# FAT42.net
KiCad netlist of a schematic drawn in Altium Designer
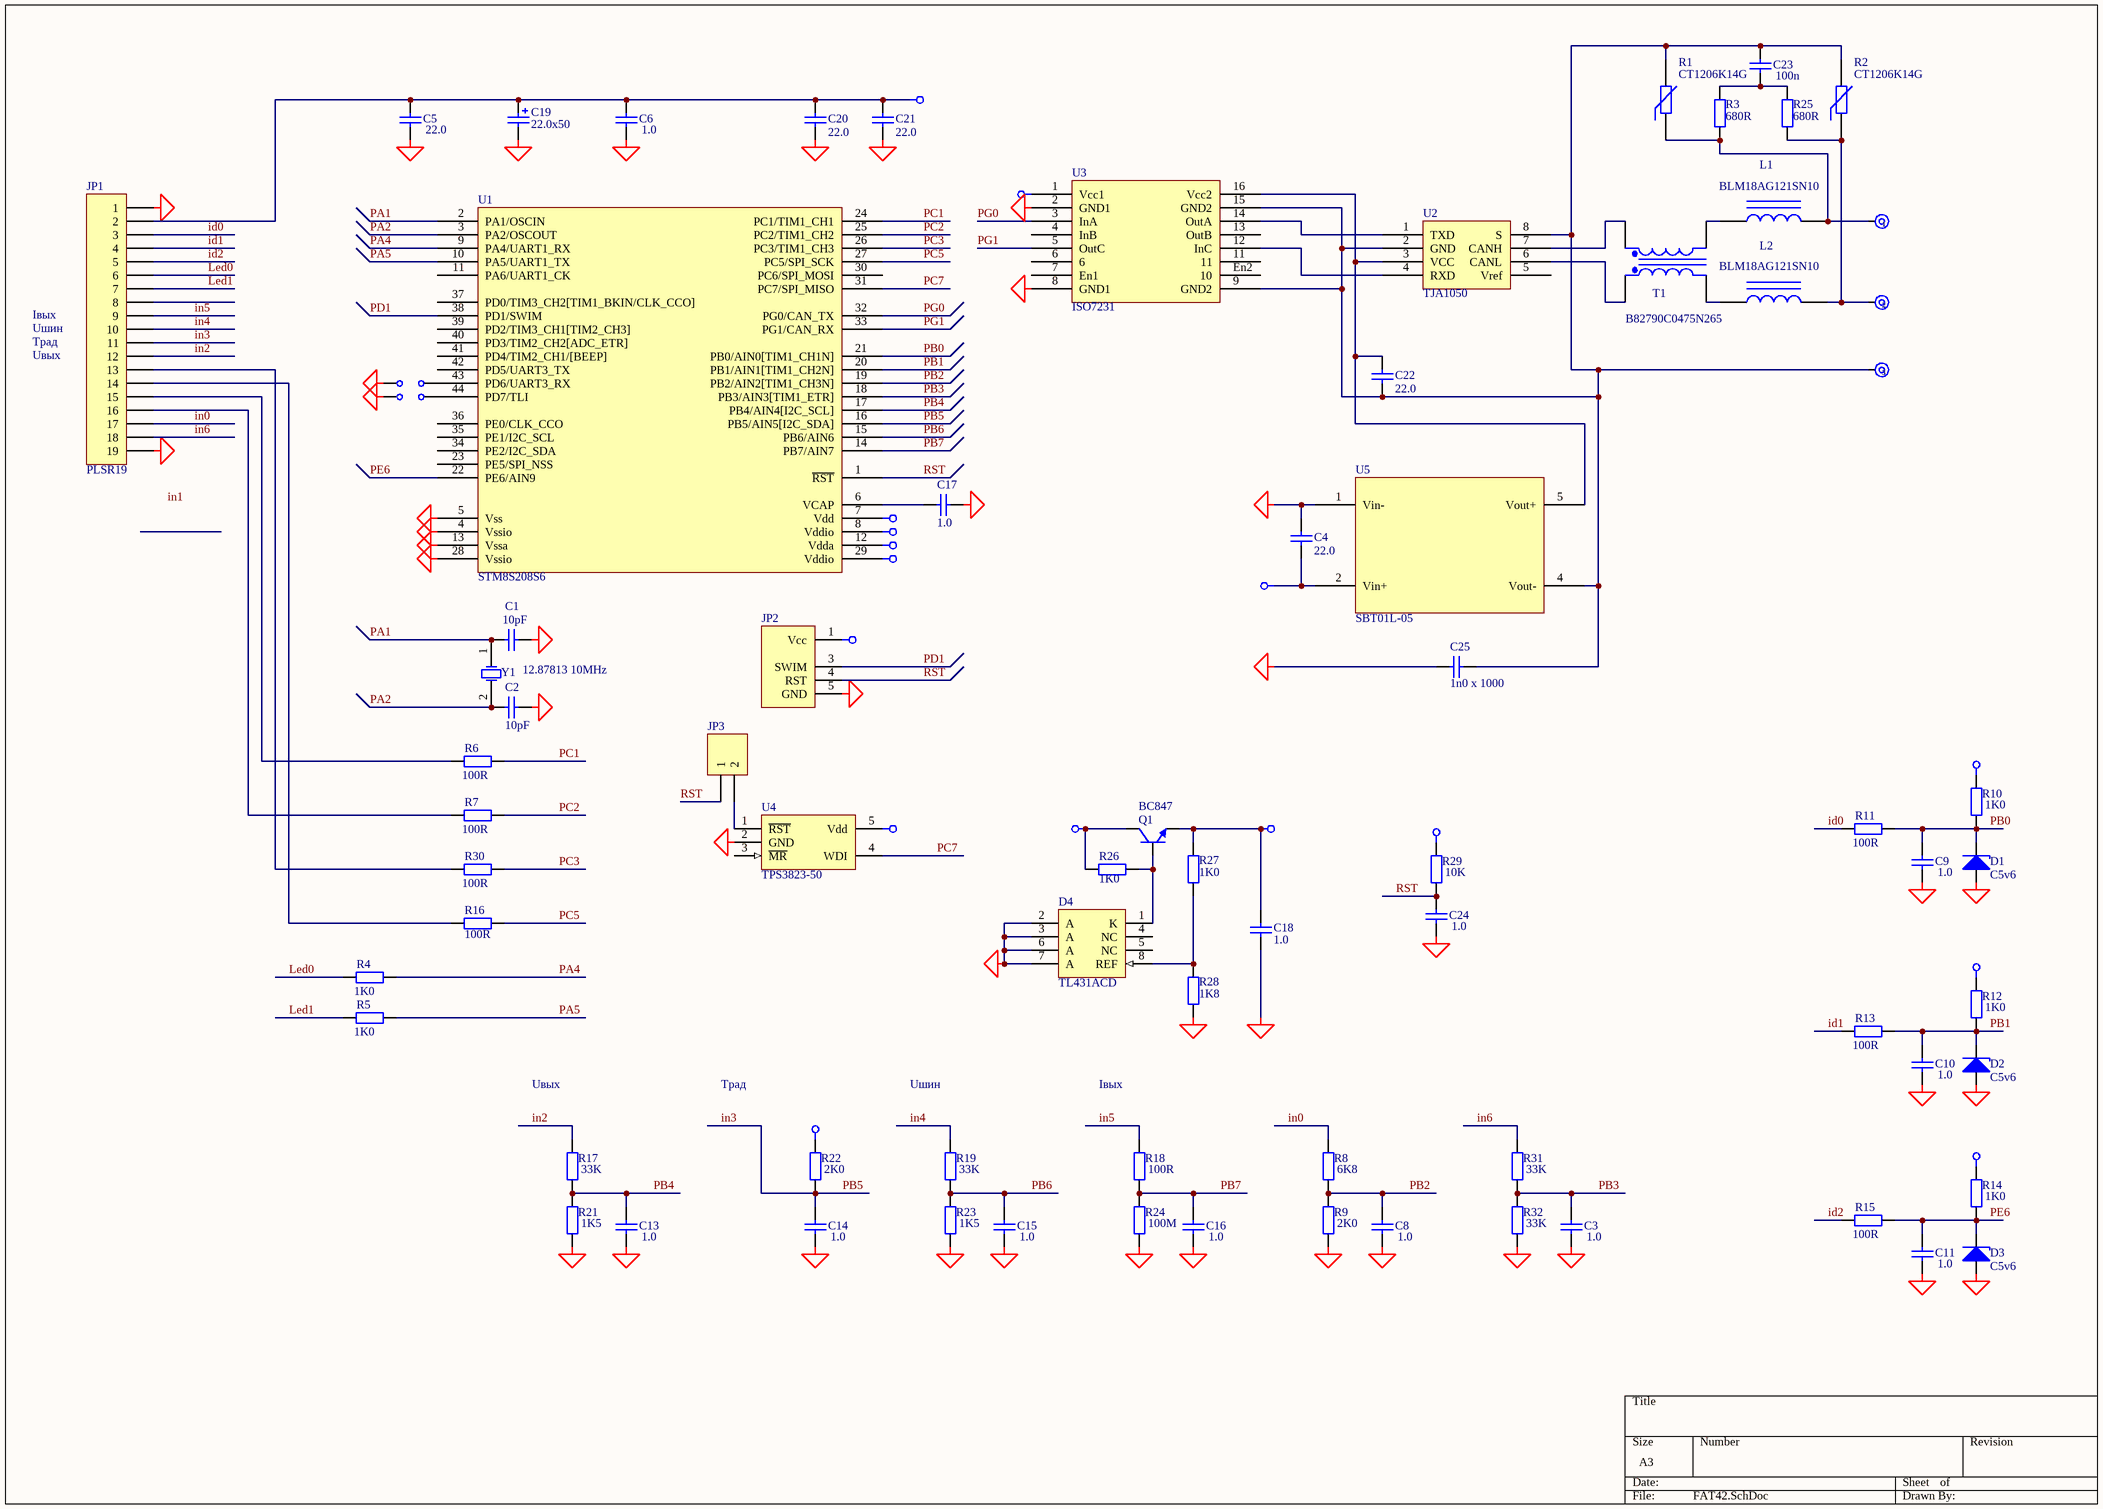
[diagram p0: FAT42.SchDoc]

(export (version "E")
  (design (tool "Eeschema 10.0.6"))
  (components
    (comp (ref "1")
      (value "~")
      (footprint "PIN2R")
      (description "Socket")
      (fields (field (name "MANUFACTURER") "Generic Components") (field (name "PUBLISHER") "Altium Limited"))
      (libsource (lib "PAL") (part "Socket_Ring"))
    )
    (comp (ref "2")
      (value "~")
      (footprint "PIN2R")
      (description "Socket")
      (fields (field (name "MANUFACTURER") "Generic Components") (field (name "PUBLISHER") "Altium Limited"))
      (libsource (lib "PAL") (part "Socket_Ring"))
    )
    (comp (ref "3")
      (value "~")
      (footprint "PIN2R")
      (description "Socket")
      (fields (field (name "MANUFACTURER") "Generic Components") (field (name "PUBLISHER") "Altium Limited"))
      (libsource (lib "PAL") (part "Socket_Ring"))
    )
    (comp (ref "C1")
      (value "10pF")
      (footprint "_0603")
      (description "Capacitor (Semiconductor SIM Model)")
      (fields (field (name "MANUFACTURER") "Generic Components") (field (name "PUBLISHER") "Altium Limited"))
      (libsource (lib "Miscellaneous Devices") (part "Cap Semi"))
    )
    (comp (ref "C2")
      (value "10pF")
      (footprint "_0603")
      (description "Capacitor (Semiconductor SIM Model)")
      (fields (field (name "MANUFACTURER") "Generic Components") (field (name "PUBLISHER") "Altium Limited"))
      (libsource (lib "Miscellaneous Devices") (part "Cap Semi"))
    )
    (comp (ref "C3")
      (value "1.0")
      (footprint "_0603")
      (description "Capacitor (Semiconductor SIM Model)")
      (fields (field (name "MANUFACTURER") "Generic Components") (field (name "PUBLISHER") "Altium Limited"))
      (libsource (lib "Miscellaneous Devices") (part "Cap Semi"))
    )
    (comp (ref "C4")
      (value "22.0")
      (footprint "_1206")
      (description "Capacitor (Semiconductor SIM Model)")
      (fields (field (name "MANUFACTURER") "Generic Components") (field (name "PUBLISHER") "Altium Limited"))
      (libsource (lib "Miscellaneous Devices") (part "Cap Semi"))
    )
    (comp (ref "C5")
      (value "22.0")
      (footprint "_1206")
      (description "Capacitor (Semiconductor SIM Model)")
      (fields (field (name "MANUFACTURER") "Generic Components") (field (name "PUBLISHER") "Altium Limited"))
      (libsource (lib "Miscellaneous Devices") (part "Cap Semi"))
    )
    (comp (ref "C6")
      (value "1.0")
      (footprint "_1206")
      (description "Capacitor (Semiconductor SIM Model)")
      (fields (field (name "MANUFACTURER") "Generic Components") (field (name "PUBLISHER") "Altium Limited"))
      (libsource (lib "Miscellaneous Devices") (part "Cap Semi"))
    )
    (comp (ref "C8")
      (value "1.0")
      (footprint "_0603")
      (description "Capacitor (Semiconductor SIM Model)")
      (fields (field (name "MANUFACTURER") "Generic Components") (field (name "PUBLISHER") "Altium Limited"))
      (libsource (lib "Miscellaneous Devices") (part "Cap Semi"))
    )
    (comp (ref "C9")
      (value "1.0")
      (footprint "_0603")
      (description "Capacitor (Semiconductor SIM Model)")
      (fields (field (name "MANUFACTURER") "Generic Components") (field (name "PUBLISHER") "Altium Limited"))
      (libsource (lib "Miscellaneous Devices") (part "Cap Semi"))
    )
    (comp (ref "C10")
      (value "1.0")
      (footprint "_0603")
      (description "Capacitor (Semiconductor SIM Model)")
      (fields (field (name "MANUFACTURER") "Generic Components") (field (name "PUBLISHER") "Altium Limited"))
      (libsource (lib "Miscellaneous Devices") (part "Cap Semi"))
    )
    (comp (ref "C11")
      (value "1.0")
      (footprint "_0603")
      (description "Capacitor (Semiconductor SIM Model)")
      (fields (field (name "MANUFACTURER") "Generic Components") (field (name "PUBLISHER") "Altium Limited"))
      (libsource (lib "Miscellaneous Devices") (part "Cap Semi"))
    )
    (comp (ref "C13")
      (value "1.0")
      (footprint "_0603")
      (description "Capacitor (Semiconductor SIM Model)")
      (fields (field (name "MANUFACTURER") "Generic Components") (field (name "PUBLISHER") "Altium Limited"))
      (libsource (lib "Miscellaneous Devices") (part "Cap Semi"))
    )
    (comp (ref "C14")
      (value "1.0")
      (footprint "_0603")
      (description "Capacitor (Semiconductor SIM Model)")
      (fields (field (name "MANUFACTURER") "Generic Components") (field (name "PUBLISHER") "Altium Limited"))
      (libsource (lib "Miscellaneous Devices") (part "Cap Semi"))
    )
    (comp (ref "C15")
      (value "1.0")
      (footprint "_0603")
      (description "Capacitor (Semiconductor SIM Model)")
      (fields (field (name "MANUFACTURER") "Generic Components") (field (name "PUBLISHER") "Altium Limited"))
      (libsource (lib "Miscellaneous Devices") (part "Cap Semi"))
    )
    (comp (ref "C16")
      (value "1.0")
      (footprint "_0603")
      (description "Capacitor (Semiconductor SIM Model)")
      (fields (field (name "MANUFACTURER") "Generic Components") (field (name "PUBLISHER") "Altium Limited"))
      (libsource (lib "Miscellaneous Devices") (part "Cap Semi"))
    )
    (comp (ref "C17")
      (value "1.0")
      (footprint "_0603")
      (description "Capacitor (Semiconductor SIM Model)")
      (fields (field (name "MANUFACTURER") "Generic Components") (field (name "PUBLISHER") "Altium Limited"))
      (libsource (lib "Miscellaneous Devices") (part "Cap Semi"))
    )
    (comp (ref "C18")
      (value "1.0")
      (footprint "_0603")
      (description "Capacitor (Semiconductor SIM Model)")
      (fields (field (name "MANUFACTURER") "Generic Components") (field (name "PUBLISHER") "Altium Limited"))
      (libsource (lib "Miscellaneous Devices") (part "Cap Semi"))
    )
    (comp (ref "C19")
      (value "22.0x50")
      (footprint "el3")
      (description "Polarized Capacitor (Radial)")
      (fields (field (name "MANUFACTURER") "Generic Components") (field (name "PUBLISHER") "Altium Limited"))
      (libsource (lib "PAL") (part "Cap Pol1"))
    )
    (comp (ref "C20")
      (value "22.0")
      (footprint "_1206")
      (description "Capacitor (Semiconductor SIM Model)")
      (fields (field (name "MANUFACTURER") "Generic Components") (field (name "PUBLISHER") "Altium Limited"))
      (libsource (lib "Miscellaneous Devices") (part "Cap Semi"))
    )
    (comp (ref "C21")
      (value "22.0")
      (footprint "_1206")
      (description "Capacitor (Semiconductor SIM Model)")
      (fields (field (name "MANUFACTURER") "Generic Components") (field (name "PUBLISHER") "Altium Limited"))
      (libsource (lib "Miscellaneous Devices") (part "Cap Semi"))
    )
    (comp (ref "C22")
      (value "22.0")
      (footprint "_1206")
      (description "Capacitor (Semiconductor SIM Model)")
      (fields (field (name "MANUFACTURER") "Generic Components") (field (name "PUBLISHER") "Altium Limited"))
      (libsource (lib "Miscellaneous Devices") (part "Cap Semi"))
    )
    (comp (ref "C23")
      (value "100n")
      (footprint "_0603")
      (description "Capacitor (Semiconductor SIM Model)")
      (fields (field (name "MANUFACTURER") "Generic Components") (field (name "PUBLISHER") "Altium Limited"))
      (libsource (lib "Miscellaneous Devices") (part "Cap Semi"))
    )
    (comp (ref "C24")
      (value "1.0")
      (footprint "_0603")
      (description "Capacitor (Semiconductor SIM Model)")
      (fields (field (name "MANUFACTURER") "Generic Components") (field (name "PUBLISHER") "Altium Limited"))
      (libsource (lib "Miscellaneous Devices") (part "Cap Semi"))
    )
    (comp (ref "C25")
      (value "1n0 x 1000")
      (footprint "_1206")
      (description "Capacitor (Semiconductor SIM Model)")
      (fields (field (name "MANUFACTURER") "Generic Components") (field (name "PUBLISHER") "Altium Limited"))
      (libsource (lib "Miscellaneous Devices") (part "Cap Semi"))
    )
    (comp (ref "D1")
      (value "C5v6")
      (footprint "_1206d")
      (description "Default Diode")
      (fields (field (name "MANUFACTURER") "Generic Components") (field (name "PUBLISHER") "Altium Limited"))
      (libsource (lib "PAL") (part "Zener"))
    )
    (comp (ref "D2")
      (value "C5v6")
      (footprint "_1206d")
      (description "Default Diode")
      (fields (field (name "MANUFACTURER") "Generic Components") (field (name "PUBLISHER") "Altium Limited"))
      (libsource (lib "PAL") (part "Zener"))
    )
    (comp (ref "D3")
      (value "C5v6")
      (footprint "_1206d")
      (description "Default Diode")
      (fields (field (name "MANUFACTURER") "Generic Components") (field (name "PUBLISHER") "Altium Limited"))
      (libsource (lib "PAL") (part "Zener"))
    )
    (comp (ref "D4")
      (value "TL431ACD")
      (footprint "SO-G8")
      (description "Programmable Precision Reference")
      (fields (field (name "MANUFACTURER") "Motorola") (field (name "PUBLISHER") "Altium Limited"))
      (libsource (lib "Motorola Power Management Voltage Reference") (part "TL431ACD"))
    )
    (comp (ref "J1")
      (value "~")
      (footprint "jmp")
      (description "Switch")
      (fields (field (name "MANUFACTURER") "Generic Components") (field (name "PUBLISHER") "Altium Limited"))
      (libsource (lib "PAL") (part "JMP"))
    )
    (comp (ref "J2")
      (value "~")
      (footprint "jmp")
      (description "Switch")
      (fields (field (name "MANUFACTURER") "Generic Components") (field (name "PUBLISHER") "Altium Limited"))
      (libsource (lib "PAL") (part "JMP"))
    )
    (comp (ref "JP1")
      (value "PLSR19")
      (footprint "HDR1X19")
      (description "Header, 19-Pin")
      (fields (field (name "MANUFACTURER") "Generic Components") (field (name "PUBLISHER") "Altium Limited"))
      (libsource (lib "Miscellaneous Connectors") (part "Header 19"))
    )
    (comp (ref "JP2") (value "~") (footprint "HDR1X5_uart") (libsource (lib "PAL") (part "SWIM_CONN")))
    (comp (ref "JP3")
      (value "PLS2")
      (footprint "HDR1X2")
      (description "Header, 2-Pin")
      (fields (field (name "MANUFACTURER") "Generic Components") (field (name "PUBLISHER") "Altium Limited"))
      (libsource (lib "Miscellaneous Connectors") (part "Header 2"))
    )
    (comp (ref "L1")
      (value "BLM18AG121SN10")
      (footprint "_1206")
      (description "Magnetic-Core Inductor")
      (fields (field (name "MANUFACTURER") "Generic Components") (field (name "PUBLISHER") "Altium Limited"))
      (libsource (lib "Miscellaneous Devices") (part "Inductor Iron"))
    )
    (comp (ref "L2")
      (value "BLM18AG121SN10")
      (footprint "_1206")
      (description "Magnetic-Core Inductor")
      (fields (field (name "MANUFACTURER") "Generic Components") (field (name "PUBLISHER") "Altium Limited"))
      (libsource (lib "Miscellaneous Devices") (part "Inductor Iron"))
    )
    (comp (ref "Q1")
      (value "BC847")
      (footprint "SO-G3")
      (description "General Purpose Transistor NPN Silicon")
      (fields (field (name "MANUFACTURER") "Motorola") (field (name "PUBLISHER") "Altium Limited"))
      (libsource (lib "PAL") (part "BC847ALT1"))
    )
    (comp (ref "R1")
      (value "CT1206K14G")
      (footprint "_1206")
      (description "Varistor (Voltage-Sensitive Resistor)")
      (fields (field (name "MANUFACTURER") "Generic Components") (field (name "PUBLISHER") "Altium Limited"))
      (libsource (lib "Miscellaneous Devices") (part "Res Varistor"))
    )
    (comp (ref "R2")
      (value "CT1206K14G")
      (footprint "_1206")
      (description "Varistor (Voltage-Sensitive Resistor)")
      (fields (field (name "MANUFACTURER") "Generic Components") (field (name "PUBLISHER") "Altium Limited"))
      (libsource (lib "Miscellaneous Devices") (part "Res Varistor"))
    )
    (comp (ref "R3")
      (value "680R")
      (footprint "_0603")
      (description "Resistor")
      (fields (field (name "MANUFACTURER") "Generic Components") (field (name "PUBLISHER") "Altium Limited"))
      (libsource (lib "Miscellaneous Devices") (part "Res2"))
    )
    (comp (ref "R4")
      (value "1K0")
      (footprint "_0603")
      (description "Resistor")
      (fields (field (name "MANUFACTURER") "Generic Components") (field (name "PUBLISHER") "Altium Limited"))
      (libsource (lib "Miscellaneous Devices") (part "Res2"))
    )
    (comp (ref "R5")
      (value "1K0")
      (footprint "_0603")
      (description "Resistor")
      (fields (field (name "MANUFACTURER") "Generic Components") (field (name "PUBLISHER") "Altium Limited"))
      (libsource (lib "Miscellaneous Devices") (part "Res2"))
    )
    (comp (ref "R6")
      (value "100R")
      (footprint "_0603")
      (description "Resistor")
      (fields (field (name "MANUFACTURER") "Generic Components") (field (name "PUBLISHER") "Altium Limited"))
      (libsource (lib "") (part "Res2_2"))
    )
    (comp (ref "R7")
      (value "100R")
      (footprint "_0603")
      (description "Resistor")
      (fields (field (name "MANUFACTURER") "Generic Components") (field (name "PUBLISHER") "Altium Limited"))
      (libsource (lib "") (part "Res2_2"))
    )
    (comp (ref "R8")
      (value "6K8")
      (footprint "_0603")
      (description "Resistor")
      (fields (field (name "MANUFACTURER") "Generic Components") (field (name "PUBLISHER") "Altium Limited"))
      (libsource (lib "") (part "Res2_1"))
    )
    (comp (ref "R9")
      (value "2K0")
      (footprint "_0603")
      (description "Resistor")
      (fields (field (name "MANUFACTURER") "Generic Components") (field (name "PUBLISHER") "Altium Limited"))
      (libsource (lib "") (part "Res2_1"))
    )
    (comp (ref "R10")
      (value "1K0")
      (footprint "_0603")
      (description "Resistor")
      (fields (field (name "MANUFACTURER") "Generic Components") (field (name "PUBLISHER") "Altium Limited"))
      (libsource (lib "") (part "Res2_3"))
    )
    (comp (ref "R11")
      (value "100R")
      (footprint "_0603")
      (description "Resistor")
      (fields (field (name "MANUFACTURER") "Generic Components") (field (name "PUBLISHER") "Altium Limited"))
      (libsource (lib "") (part "Res2_2"))
    )
    (comp (ref "R12")
      (value "1K0")
      (footprint "_0603")
      (description "Resistor")
      (fields (field (name "MANUFACTURER") "Generic Components") (field (name "PUBLISHER") "Altium Limited"))
      (libsource (lib "") (part "Res2_3"))
    )
    (comp (ref "R13")
      (value "100R")
      (footprint "_0603")
      (description "Resistor")
      (fields (field (name "MANUFACTURER") "Generic Components") (field (name "PUBLISHER") "Altium Limited"))
      (libsource (lib "") (part "Res2_2"))
    )
    (comp (ref "R14")
      (value "1K0")
      (footprint "_0603")
      (description "Resistor")
      (fields (field (name "MANUFACTURER") "Generic Components") (field (name "PUBLISHER") "Altium Limited"))
      (libsource (lib "") (part "Res2_3"))
    )
    (comp (ref "R15")
      (value "100R")
      (footprint "_0603")
      (description "Resistor")
      (fields (field (name "MANUFACTURER") "Generic Components") (field (name "PUBLISHER") "Altium Limited"))
      (libsource (lib "") (part "Res2_2"))
    )
    (comp (ref "R16")
      (value "100R")
      (footprint "_0603")
      (description "Resistor")
      (fields (field (name "MANUFACTURER") "Generic Components") (field (name "PUBLISHER") "Altium Limited"))
      (libsource (lib "") (part "Res2_2"))
    )
    (comp (ref "R17")
      (value "33K")
      (footprint "_1206")
      (description "Resistor")
      (fields (field (name "MANUFACTURER") "Generic Components") (field (name "PUBLISHER") "Altium Limited"))
      (libsource (lib "") (part "Res2_1"))
    )
    (comp (ref "R18")
      (value "100R")
      (footprint "_0603")
      (description "Resistor")
      (fields (field (name "MANUFACTURER") "Generic Components") (field (name "PUBLISHER") "Altium Limited"))
      (libsource (lib "") (part "Res2_1"))
    )
    (comp (ref "R19")
      (value "33K")
      (footprint "_1206")
      (description "Resistor")
      (fields (field (name "MANUFACTURER") "Generic Components") (field (name "PUBLISHER") "Altium Limited"))
      (libsource (lib "") (part "Res2_1"))
    )
    (comp (ref "R21")
      (value "1K5")
      (footprint "_0603")
      (description "Resistor")
      (fields (field (name "MANUFACTURER") "Generic Components") (field (name "PUBLISHER") "Altium Limited"))
      (libsource (lib "") (part "Res2_1"))
    )
    (comp (ref "R22")
      (value "2K0")
      (footprint "_0603")
      (description "Resistor")
      (fields (field (name "MANUFACTURER") "Generic Components") (field (name "PUBLISHER") "Altium Limited"))
      (libsource (lib "") (part "Res2_1"))
    )
    (comp (ref "R23")
      (value "1K5")
      (footprint "_0603")
      (description "Resistor")
      (fields (field (name "MANUFACTURER") "Generic Components") (field (name "PUBLISHER") "Altium Limited"))
      (libsource (lib "") (part "Res2_1"))
    )
    (comp (ref "R24")
      (value "100M")
      (footprint "_0603")
      (description "Resistor")
      (fields (field (name "MANUFACTURER") "Generic Components") (field (name "PUBLISHER") "Altium Limited"))
      (libsource (lib "") (part "Res2_1"))
    )
    (comp (ref "R25")
      (value "680R")
      (footprint "_0603")
      (description "Resistor")
      (fields (field (name "MANUFACTURER") "Generic Components") (field (name "PUBLISHER") "Altium Limited"))
      (libsource (lib "Miscellaneous Devices") (part "Res2"))
    )
    (comp (ref "R26")
      (value "1K0")
      (footprint "_0603")
      (description "Resistor")
      (fields (field (name "MANUFACTURER") "Generic Components") (field (name "PUBLISHER") "Altium Limited"))
      (libsource (lib "") (part "Res2_4"))
    )
    (comp (ref "R27")
      (value "1K0")
      (footprint "_0603")
      (description "Resistor")
      (fields (field (name "MANUFACTURER") "Generic Components") (field (name "PUBLISHER") "Altium Limited"))
      (libsource (lib "Miscellaneous Devices") (part "Res2"))
    )
    (comp (ref "R28")
      (value "1K8")
      (footprint "_0603")
      (description "Resistor")
      (fields (field (name "MANUFACTURER") "Generic Components") (field (name "PUBLISHER") "Altium Limited"))
      (libsource (lib "Miscellaneous Devices") (part "Res2"))
    )
    (comp (ref "R29")
      (value "10K")
      (footprint "_0603")
      (description "Resistor")
      (fields (field (name "MANUFACTURER") "Generic Components") (field (name "PUBLISHER") "Altium Limited"))
      (libsource (lib "") (part "Res2_3"))
    )
    (comp (ref "R30")
      (value "100R")
      (footprint "_0603")
      (description "Resistor")
      (fields (field (name "MANUFACTURER") "Generic Components") (field (name "PUBLISHER") "Altium Limited"))
      (libsource (lib "") (part "Res2_2"))
    )
    (comp (ref "R31")
      (value "33K")
      (footprint "_0603")
      (description "Resistor")
      (fields (field (name "MANUFACTURER") "Generic Components") (field (name "PUBLISHER") "Altium Limited"))
      (libsource (lib "") (part "Res2_1"))
    )
    (comp (ref "R32")
      (value "33K")
      (footprint "_0603")
      (description "Resistor")
      (fields (field (name "MANUFACTURER") "Generic Components") (field (name "PUBLISHER") "Altium Limited"))
      (libsource (lib "") (part "Res2_1"))
    )
    (comp (ref "T1")
      (value "B82790C0475N265")
      (footprint "B82790")
      (description "Transformer (Coupled Inductor Model)")
      (fields (field (name "MANUFACTURER") "Generic Components") (field (name "PUBLISHER") "Altium Limited"))
      (libsource (lib "Miscellaneous Devices") (part "Trans Cupl"))
    )
    (comp (ref "U1")
      (value "STM8S208S6")
      (footprint "QFP10X10-G44/G10N")
      (libsource (lib "PAL") (part "STM8S208S6"))
    )
    (comp (ref "U2") (value "TJA1050") (footprint "SO-G8/D5") (libsource (lib "PAL") (part "TJA1050")))
    (comp (ref "U3") (value "ISO7231") (footprint "SO-G16/D10.4") (libsource (lib "PAL") (part "ISO7231")))
    (comp (ref "U4")
      (value "TPS3823-50")
      (footprint "SO-G5/P.95")
      (description "Reset IC")
      (fields
        (field (name "MANUFACTURER") "National Semiconductor")
        (field (name "PUBLISHER") "Altium Limited")
      )
      (libsource (lib "PAL") (part "TPS3823"))
    )
    (comp (ref "U5") (value "SBT01L-05") (footprint "SBT01L") (libsource (lib "PAL") (part "SBT01L")))
    (comp (ref "Y1")
      (value "12.87813 10MHz")
      (footprint "hc49/us")
      (description "Crystal Oscillator")
      (fields (field (name "MANUFACTURER") "Generic Components") (field (name "PUBLISHER") "Altium Limited"))
      (libsource (lib "Miscellaneous Devices") (part "XTAL"))
    )
  )
  (nets
    (net (code "1") (name "+5v") (class "Default")
      (node (ref "C19") (pin "1") (pinfunction "1_1") (pintype "passive"))
      (node (ref "C20") (pin "1") (pinfunction "1_1") (pintype "passive"))
      (node (ref "C21") (pin "1") (pinfunction "1_1") (pintype "passive"))
      (node (ref "C4") (pin "2") (pinfunction "2_2") (pintype "passive"))
      (node (ref "C5") (pin "2") (pinfunction "2_2") (pintype "passive"))
      (node (ref "C6") (pin "2") (pinfunction "2_2") (pintype "passive"))
      (node (ref "JP1") (pin "2") (pinfunction "2_2") (pintype "passive"))
      (node (ref "JP2") (pin "1") (pinfunction "Vcc_1") (pintype "passive"))
      (node (ref "Q1") (pin "3") (pinfunction "C_3") (pintype "passive"))
      (node (ref "R10") (pin "1") (pinfunction "1_1") (pintype "passive"))
      (node (ref "R12") (pin "1") (pinfunction "1_1") (pintype "passive"))
      (node (ref "R14") (pin "1") (pinfunction "1_1") (pintype "passive"))
      (node (ref "R22") (pin "2") (pinfunction "2_2") (pintype "passive"))
      (node (ref "R26") (pin "1") (pinfunction "1_1") (pintype "passive"))
      (node (ref "R29") (pin "1") (pinfunction "1_1") (pintype "passive"))
      (node (ref "U1") (pin "29") (pinfunction "Vddio_29") (pintype "passive"))
      (node (ref "U1") (pin "7") (pinfunction "Vdd_7") (pintype "passive"))
      (node (ref "U1") (pin "8") (pinfunction "Vddio_8") (pintype "passive"))
      (node (ref "U3") (pin "1") (pinfunction "Vcc1_1") (pintype "passive"))
      (node (ref "U4") (pin "5") (pinfunction "Vdd_5") (pintype "power_in"))
      (node (ref "U5") (pin "2") (pinfunction "Vin+_2") (pintype "passive"))
    )
    (net (code "2") (name "/Led0") (class "Default")
      (node (ref "JP1") (pin "6") (pinfunction "6_6") (pintype "passive"))
      (node (ref "R4") (pin "1") (pinfunction "1_1") (pintype "passive"))
    )
    (net (code "3") (name "/Led1") (class "Default")
      (node (ref "JP1") (pin "7") (pinfunction "7_7") (pintype "passive"))
      (node (ref "R5") (pin "1") (pinfunction "1_1") (pintype "passive"))
    )
    (net (code "4") (name "/PA1") (class "Default")
      (node (ref "C1") (pin "2") (pinfunction "2_2") (pintype "passive"))
      (node (ref "U1") (pin "2") (pinfunction "PA1/OSCIN_2") (pintype "passive"))
      (node (ref "Y1") (pin "1") (pinfunction "OSC1_1") (pintype "passive"))
    )
    (net (code "5") (name "/PA2") (class "Default")
      (node (ref "C2") (pin "2") (pinfunction "2_2") (pintype "passive"))
      (node (ref "U1") (pin "3") (pinfunction "PA2/OSCOUT_3") (pintype "passive"))
      (node (ref "Y1") (pin "2") (pinfunction "OSC2_2") (pintype "passive"))
    )
    (net (code "6") (name "/PA4") (class "Default")
      (node (ref "R4") (pin "2") (pinfunction "2_2") (pintype "passive"))
      (node (ref "U1") (pin "9") (pinfunction "PA4/UART1_RX_9") (pintype "passive"))
    )
    (net (code "7") (name "/PA5") (class "Default")
      (node (ref "R5") (pin "2") (pinfunction "2_2") (pintype "passive"))
      (node (ref "U1") (pin "10") (pinfunction "PA5/UART1_TX_10") (pintype "passive"))
    )
    (net (code "8") (name "/PB0") (class "Default")
      (node (ref "C9") (pin "2") (pinfunction "2_2") (pintype "passive"))
      (node (ref "D1") (pin "2") (pinfunction "K_2") (pintype "passive"))
      (node (ref "R10") (pin "2") (pinfunction "2_2") (pintype "passive"))
      (node (ref "R11") (pin "1") (pinfunction "1_1") (pintype "passive"))
      (node (ref "U1") (pin "21") (pinfunction "PB0/AIN0[TIM1_CH1N]_21") (pintype "passive"))
    )
    (net (code "9") (name "/PB1") (class "Default")
      (node (ref "C10") (pin "2") (pinfunction "2_2") (pintype "passive"))
      (node (ref "D2") (pin "2") (pinfunction "K_2") (pintype "passive"))
      (node (ref "R12") (pin "2") (pinfunction "2_2") (pintype "passive"))
      (node (ref "R13") (pin "1") (pinfunction "1_1") (pintype "passive"))
      (node (ref "U1") (pin "20") (pinfunction "PB1/AIN1[TIM1_CH2N]_20") (pintype "passive"))
    )
    (net (code "10") (name "/PB2") (class "Default")
      (node (ref "C8") (pin "2") (pinfunction "2_2") (pintype "passive"))
      (node (ref "R8") (pin "1") (pinfunction "1_1") (pintype "passive"))
      (node (ref "R9") (pin "2") (pinfunction "2_2") (pintype "passive"))
      (node (ref "U1") (pin "19") (pinfunction "PB2/AIN2[TIM1_CH3N]_19") (pintype "passive"))
    )
    (net (code "11") (name "/PB3") (class "Default")
      (node (ref "C3") (pin "2") (pinfunction "2_2") (pintype "passive"))
      (node (ref "R31") (pin "1") (pinfunction "1_1") (pintype "passive"))
      (node (ref "R32") (pin "2") (pinfunction "2_2") (pintype "passive"))
      (node (ref "U1") (pin "18") (pinfunction "PB3/AIN3[TIM1_ETR]_18") (pintype "passive"))
    )
    (net (code "12") (name "/PB4") (class "Default")
      (node (ref "C13") (pin "2") (pinfunction "2_2") (pintype "passive"))
      (node (ref "R17") (pin "1") (pinfunction "1_1") (pintype "passive"))
      (node (ref "R21") (pin "2") (pinfunction "2_2") (pintype "passive"))
      (node (ref "U1") (pin "17") (pinfunction "PB4/AIN4[I2C_SCL]_17") (pintype "passive"))
    )
    (net (code "13") (name "/PB5") (class "Default")
      (node (ref "C14") (pin "2") (pinfunction "2_2") (pintype "passive"))
      (node (ref "JP1") (pin "11") (pinfunction "11_11") (pintype "passive"))
      (node (ref "R22") (pin "1") (pinfunction "1_1") (pintype "passive"))
      (node (ref "U1") (pin "16") (pinfunction "PB5/AIN5[I2C_SDA]_16") (pintype "passive"))
    )
    (net (code "14") (name "/PB6") (class "Default")
      (node (ref "C15") (pin "2") (pinfunction "2_2") (pintype "passive"))
      (node (ref "R19") (pin "1") (pinfunction "1_1") (pintype "passive"))
      (node (ref "R23") (pin "2") (pinfunction "2_2") (pintype "passive"))
      (node (ref "U1") (pin "15") (pinfunction "PB6/AIN6_15") (pintype "passive"))
    )
    (net (code "15") (name "/PB7") (class "Default")
      (node (ref "C16") (pin "2") (pinfunction "2_2") (pintype "passive"))
      (node (ref "R18") (pin "1") (pinfunction "1_1") (pintype "passive"))
      (node (ref "R24") (pin "2") (pinfunction "2_2") (pintype "passive"))
      (node (ref "U1") (pin "14") (pinfunction "PB7/AIN7_14") (pintype "passive"))
    )
    (net (code "16") (name "/PC1") (class "Default")
      (node (ref "R6") (pin "1") (pinfunction "1_1") (pintype "passive"))
      (node (ref "U1") (pin "24") (pinfunction "PC1/TIM1_CH1_24") (pintype "passive"))
    )
    (net (code "17") (name "/PC2") (class "Default")
      (node (ref "R7") (pin "1") (pinfunction "1_1") (pintype "passive"))
      (node (ref "U1") (pin "25") (pinfunction "PC2/TIM1_CH2_25") (pintype "passive"))
    )
    (net (code "18") (name "/PC3") (class "Default")
      (node (ref "R30") (pin "1") (pinfunction "1_1") (pintype "passive"))
      (node (ref "U1") (pin "26") (pinfunction "PC3/TIM1_CH3_26") (pintype "passive"))
    )
    (net (code "19") (name "/PC5") (class "Default")
      (node (ref "R16") (pin "1") (pinfunction "1_1") (pintype "passive"))
      (node (ref "U1") (pin "27") (pinfunction "PC5/SPI_SCK_27") (pintype "passive"))
    )
    (net (code "20") (name "/PC7") (class "Default")
      (node (ref "U1") (pin "31") (pinfunction "PC7/SPI_MISO_31") (pintype "passive"))
      (node (ref "U4") (pin "4") (pinfunction "WDI_4") (pintype "passive"))
    )
    (net (code "21") (name "/PD1") (class "Default")
      (node (ref "JP2") (pin "3") (pinfunction "SWIM_3") (pintype "passive"))
      (node (ref "U1") (pin "38") (pinfunction "PD1/SWIM_38") (pintype "passive"))
    )
    (net (code "22") (name "/PE6") (class "Default")
      (node (ref "C11") (pin "2") (pinfunction "2_2") (pintype "passive"))
      (node (ref "D3") (pin "2") (pinfunction "K_2") (pintype "passive"))
      (node (ref "R14") (pin "2") (pinfunction "2_2") (pintype "passive"))
      (node (ref "R15") (pin "1") (pinfunction "1_1") (pintype "passive"))
      (node (ref "U1") (pin "22") (pinfunction "PE6/AIN9_22") (pintype "passive"))
    )
    (net (code "23") (name "/PG0") (class "Default")
      (node (ref "U1") (pin "32") (pinfunction "PG0/CAN_TX_32") (pintype "passive"))
      (node (ref "U3") (pin "3") (pinfunction "InA_3") (pintype "passive"))
    )
    (net (code "24") (name "/PG1") (class "Default")
      (node (ref "U1") (pin "33") (pinfunction "PG1/CAN_RX_33") (pintype "passive"))
      (node (ref "U3") (pin "5") (pinfunction "OutC_5") (pintype "passive"))
    )
    (net (code "25") (name "/RST") (class "Default")
      (node (ref "C24") (pin "2") (pinfunction "2_2") (pintype "passive"))
      (node (ref "JP2") (pin "4") (pinfunction "RST_4") (pintype "passive"))
      (node (ref "JP3") (pin "1") (pinfunction "1_1") (pintype "passive"))
      (node (ref "R29") (pin "2") (pinfunction "2_2") (pintype "passive"))
      (node (ref "U1") (pin "1") (pinfunction "~{RST}_1") (pintype "passive"))
    )
    (net (code "26") (name "/id0") (class "Default")
      (node (ref "JP1") (pin "3") (pinfunction "3_3") (pintype "passive"))
      (node (ref "R11") (pin "2") (pinfunction "2_2") (pintype "passive"))
    )
    (net (code "27") (name "/id1") (class "Default")
      (node (ref "JP1") (pin "4") (pinfunction "4_4") (pintype "passive"))
      (node (ref "R13") (pin "2") (pinfunction "2_2") (pintype "passive"))
    )
    (net (code "28") (name "/id2") (class "Default")
      (node (ref "JP1") (pin "5") (pinfunction "5_5") (pintype "passive"))
      (node (ref "R15") (pin "2") (pinfunction "2_2") (pintype "passive"))
    )
    (net (code "29") (name "/in0") (class "Default")
      (node (ref "JP1") (pin "17") (pinfunction "17_17") (pintype "passive"))
      (node (ref "R8") (pin "2") (pinfunction "2_2") (pintype "passive"))
    )
    (net (code "31") (name "/in2") (class "Default")
      (node (ref "JP1") (pin "12") (pinfunction "12_12") (pintype "passive"))
      (node (ref "R17") (pin "2") (pinfunction "2_2") (pintype "passive"))
    )
    (net (code "32") (name "/in4") (class "Default")
      (node (ref "JP1") (pin "10") (pinfunction "10_10") (pintype "passive"))
      (node (ref "R19") (pin "2") (pinfunction "2_2") (pintype "passive"))
    )
    (net (code "33") (name "/in5") (class "Default")
      (node (ref "JP1") (pin "9") (pinfunction "9_9") (pintype "passive"))
      (node (ref "R18") (pin "2") (pinfunction "2_2") (pintype "passive"))
    )
    (net (code "34") (name "/in6") (class "Default")
      (node (ref "JP1") (pin "18") (pinfunction "18_18") (pintype "passive"))
      (node (ref "R31") (pin "2") (pinfunction "2_2") (pintype "passive"))
    )
    (net (code "35") (name "GND") (class "Default")
      (node (ref "C1") (pin "1") (pinfunction "1_1") (pintype "passive"))
      (node (ref "C10") (pin "1") (pinfunction "1_1") (pintype "passive"))
      (node (ref "C11") (pin "1") (pinfunction "1_1") (pintype "passive"))
      (node (ref "C13") (pin "1") (pinfunction "1_1") (pintype "passive"))
      (node (ref "C14") (pin "1") (pinfunction "1_1") (pintype "passive"))
      (node (ref "C15") (pin "1") (pinfunction "1_1") (pintype "passive"))
      (node (ref "C16") (pin "1") (pinfunction "1_1") (pintype "passive"))
      (node (ref "C17") (pin "1") (pinfunction "1_1") (pintype "passive"))
      (node (ref "C18") (pin "1") (pinfunction "1_1") (pintype "passive"))
      (node (ref "C19") (pin "2") (pinfunction "2_2") (pintype "passive"))
      (node (ref "C2") (pin "1") (pinfunction "1_1") (pintype "passive"))
      (node (ref "C20") (pin "2") (pinfunction "2_2") (pintype "passive"))
      (node (ref "C21") (pin "2") (pinfunction "2_2") (pintype "passive"))
      (node (ref "C24") (pin "1") (pinfunction "1_1") (pintype "passive"))
      (node (ref "C25") (pin "1") (pinfunction "1_1") (pintype "passive"))
      (node (ref "C3") (pin "1") (pinfunction "1_1") (pintype "passive"))
      (node (ref "C4") (pin "1") (pinfunction "1_1") (pintype "passive"))
      (node (ref "C5") (pin "1") (pinfunction "1_1") (pintype "passive"))
      (node (ref "C6") (pin "1") (pinfunction "1_1") (pintype "passive"))
      (node (ref "C8") (pin "1") (pinfunction "1_1") (pintype "passive"))
      (node (ref "C9") (pin "1") (pinfunction "1_1") (pintype "passive"))
      (node (ref "D1") (pin "1") (pinfunction "A_1") (pintype "passive"))
      (node (ref "D2") (pin "1") (pinfunction "A_1") (pintype "passive"))
      (node (ref "D3") (pin "1") (pinfunction "A_1") (pintype "passive"))
      (node (ref "D4") (pin "2") (pinfunction "A_2") (pintype "passive"))
      (node (ref "D4") (pin "3") (pinfunction "A_3") (pintype "passive"))
      (node (ref "D4") (pin "6") (pinfunction "A_6") (pintype "passive"))
      (node (ref "D4") (pin "7") (pinfunction "A_7") (pintype "passive"))
      (node (ref "J1") (pin "1") (pinfunction "1_1") (pintype "passive"))
      (node (ref "J2") (pin "1") (pinfunction "1_1") (pintype "passive"))
      (node (ref "JP1") (pin "1") (pinfunction "1_1") (pintype "passive"))
      (node (ref "JP1") (pin "19") (pinfunction "19_19") (pintype "passive"))
      (node (ref "JP2") (pin "5") (pinfunction "GND_5") (pintype "passive"))
      (node (ref "R21") (pin "1") (pinfunction "1_1") (pintype "passive"))
      (node (ref "R23") (pin "1") (pinfunction "1_1") (pintype "passive"))
      (node (ref "R24") (pin "1") (pinfunction "1_1") (pintype "passive"))
      (node (ref "R28") (pin "1") (pinfunction "1_1") (pintype "passive"))
      (node (ref "R32") (pin "1") (pinfunction "1_1") (pintype "passive"))
      (node (ref "R9") (pin "1") (pinfunction "1_1") (pintype "passive"))
      (node (ref "U1") (pin "13") (pinfunction "Vssa_13") (pintype "passive"))
      (node (ref "U1") (pin "28") (pinfunction "Vssio_28") (pintype "passive"))
      (node (ref "U1") (pin "4") (pinfunction "Vssio_4") (pintype "passive"))
      (node (ref "U1") (pin "5") (pinfunction "Vss_5") (pintype "passive"))
      (node (ref "U3") (pin "2") (pinfunction "GND1_2") (pintype "passive"))
      (node (ref "U3") (pin "8") (pinfunction "GND1_8") (pintype "passive"))
      (node (ref "U4") (pin "2") (pinfunction "GND_2") (pintype "power_in"))
      (node (ref "U5") (pin "1") (pinfunction "Vin-_1") (pintype "passive"))
    )
    (net (code "36") (name "Net-(1-Pad1)") (class "Default")
      (node (ref "1") (pin "1") (pinfunction "1_1") (pintype "passive"))
      (node (ref "L1") (pin "2") (pinfunction "2_2") (pintype "passive"))
      (node (ref "R1") (pin "1") (pinfunction "1_1") (pintype "passive"))
      (node (ref "R3") (pin "1") (pinfunction "1_1") (pintype "passive"))
    )
    (net (code "37") (name "Net-(2-Pad1)") (class "Default")
      (node (ref "2") (pin "1") (pinfunction "1_1") (pintype "passive"))
      (node (ref "L2") (pin "2") (pinfunction "2_2") (pintype "passive"))
      (node (ref "R2") (pin "1") (pinfunction "1_1") (pintype "passive"))
      (node (ref "R25") (pin "1") (pinfunction "1_1") (pintype "passive"))
    )
    (net (code "38") (name "Net-(C23-Pad1)") (class "Default")
      (node (ref "C23") (pin "1") (pinfunction "1_1") (pintype "passive"))
      (node (ref "R25") (pin "2") (pinfunction "2_2") (pintype "passive"))
      (node (ref "R3") (pin "2") (pinfunction "2_2") (pintype "passive"))
    )
    (net (code "39") (name "Net-(D4-K)") (class "Default")
      (node (ref "D4") (pin "1") (pinfunction "K_1") (pintype "passive"))
      (node (ref "Q1") (pin "1") (pinfunction "B_1") (pintype "passive"))
      (node (ref "R26") (pin "2") (pinfunction "2_2") (pintype "passive"))
    )
    (net (code "40") (name "Net-(D4-REF)") (class "Default")
      (node (ref "D4") (pin "8") (pinfunction "REF_8") (pintype "input"))
      (node (ref "R27") (pin "1") (pinfunction "1_1") (pintype "passive"))
      (node (ref "R28") (pin "2") (pinfunction "2_2") (pintype "passive"))
    )
    (net (code "41") (name "Net-(JP1-Pad13)") (class "Default")
      (node (ref "JP1") (pin "13") (pinfunction "13_13") (pintype "passive"))
      (node (ref "R30") (pin "2") (pinfunction "2_2") (pintype "passive"))
    )
    (net (code "42") (name "Net-(JP1-Pad14)") (class "Default")
      (node (ref "JP1") (pin "14") (pinfunction "14_14") (pintype "passive"))
      (node (ref "R16") (pin "2") (pinfunction "2_2") (pintype "passive"))
    )
    (net (code "43") (name "Net-(JP1-Pad15)") (class "Default")
      (node (ref "JP1") (pin "15") (pinfunction "15_15") (pintype "passive"))
      (node (ref "R6") (pin "2") (pinfunction "2_2") (pintype "passive"))
    )
    (net (code "44") (name "Net-(JP1-Pad16)") (class "Default")
      (node (ref "JP1") (pin "16") (pinfunction "16_16") (pintype "passive"))
      (node (ref "R7") (pin "2") (pinfunction "2_2") (pintype "passive"))
    )
    (net (code "45") (name "Net-(T1-Pri+)") (class "Default")
      (node (ref "T1") (pin "1") (pinfunction "Pri+_1") (pintype "passive"))
      (node (ref "U2") (pin "6") (pinfunction "CANL_6") (pintype "passive"))
    )
    (net (code "46") (name "Net-(T1-Pri-)") (class "Default")
      (node (ref "L2") (pin "1") (pinfunction "1_1") (pintype "passive"))
      (node (ref "T1") (pin "2") (pinfunction "Pri-_2") (pintype "passive"))
    )
    (net (code "47") (name "Net-(T1-Sec+)") (class "Default")
      (node (ref "T1") (pin "3") (pinfunction "Sec+_3") (pintype "passive"))
      (node (ref "U2") (pin "7") (pinfunction "CANH_7") (pintype "passive"))
    )
    (net (code "48") (name "Net-(T1-Sec-)") (class "Default")
      (node (ref "L1") (pin "1") (pinfunction "1_1") (pintype "passive"))
      (node (ref "T1") (pin "4") (pinfunction "Sec-_4") (pintype "passive"))
    )
    (net (code "49") (name "Net-(U1-PD6{slash}UART3_RX)") (class "Default")
      (node (ref "J1") (pin "2") (pinfunction "2_2") (pintype "passive"))
      (node (ref "U1") (pin "43") (pinfunction "PD6/UART3_RX_43") (pintype "passive"))
    )
    (net (code "50") (name "Net-(U1-PD7{slash}TLI)") (class "Default")
      (node (ref "J2") (pin "2") (pinfunction "2_2") (pintype "passive"))
      (node (ref "U1") (pin "44") (pinfunction "PD7/TLI_44") (pintype "passive"))
    )
    (net (code "51") (name "Net-(U1-VCAP)") (class "Default")
      (node (ref "C17") (pin "2") (pinfunction "2_2") (pintype "passive"))
      (node (ref "U1") (pin "6") (pinfunction "VCAP_6") (pintype "passive"))
    )
    (net (code "52") (name "Net-(U2-GND)") (class "Default")
      (node (ref "3") (pin "1") (pinfunction "1_1") (pintype "passive"))
      (node (ref "C22") (pin "2") (pinfunction "2_2") (pintype "passive"))
      (node (ref "C23") (pin "2") (pinfunction "2_2") (pintype "passive"))
      (node (ref "C25") (pin "2") (pinfunction "2_2") (pintype "passive"))
      (node (ref "R1") (pin "2") (pinfunction "2_2") (pintype "passive"))
      (node (ref "R2") (pin "2") (pinfunction "2_2") (pintype "passive"))
      (node (ref "U2") (pin "2") (pinfunction "GND_2") (pintype "passive"))
      (node (ref "U2") (pin "8") (pinfunction "S_8") (pintype "passive"))
      (node (ref "U3") (pin "15") (pinfunction "GND2_15") (pintype "passive"))
      (node (ref "U3") (pin "9") (pinfunction "GND2_9") (pintype "passive"))
      (node (ref "U5") (pin "4") (pinfunction "Vout-_4") (pintype "passive"))
    )
    (net (code "53") (name "Net-(U2-RXD)") (class "Default")
      (node (ref "U2") (pin "4") (pinfunction "RXD_4") (pintype "passive"))
      (node (ref "U3") (pin "12") (pinfunction "InC_12") (pintype "passive"))
    )
    (net (code "54") (name "Net-(U2-TXD)") (class "Default")
      (node (ref "U2") (pin "1") (pinfunction "TXD_1") (pintype "passive"))
      (node (ref "U3") (pin "14") (pinfunction "OutA_14") (pintype "passive"))
    )
    (net (code "55") (name "Net-(U2-VCC)") (class "Default")
      (node (ref "C22") (pin "1") (pinfunction "1_1") (pintype "passive"))
      (node (ref "U2") (pin "3") (pinfunction "VCC_3") (pintype "passive"))
      (node (ref "U3") (pin "16") (pinfunction "Vcc2_16") (pintype "passive"))
      (node (ref "U5") (pin "5") (pinfunction "Vout+_5") (pintype "passive"))
    )
    (net (code "56") (name "Net-(U4-~{RST})") (class "Default")
      (node (ref "JP3") (pin "2") (pinfunction "2_2") (pintype "passive"))
      (node (ref "U4") (pin "1") (pinfunction "~{RST}_1") (pintype "power_in"))
    )
    (net (code "57") (name "Uref") (class "Default")
      (node (ref "C18") (pin "2") (pinfunction "2_2") (pintype "passive"))
      (node (ref "Q1") (pin "2") (pinfunction "E_2") (pintype "passive"))
      (node (ref "R27") (pin "2") (pinfunction "2_2") (pintype "passive"))
      (node (ref "U1") (pin "12") (pinfunction "Vdda_12") (pintype "passive"))
    )
    (net (code "58") (name "unconnected-(D4-NC-Pad4)") (class "Default")
      (node (ref "D4") (pin "4") (pinfunction "NC_4") (pintype "passive"))
    )
    (net (code "59") (name "unconnected-(D4-NC-Pad5)") (class "Default")
      (node (ref "D4") (pin "5") (pinfunction "NC_5") (pintype "passive"))
    )
    (net (code "60") (name "unconnected-(JP1-Pad8)") (class "Default")
      (node (ref "JP1") (pin "8") (pinfunction "8_8") (pintype "passive"))
    )
    (net (code "61") (name "unconnected-(U1-PA6{slash}UART1_CK-Pad11)") (class "Default")
      (node (ref "U1") (pin "11") (pinfunction "PA6/UART1_CK_11") (pintype "passive"))
    )
    (net (code "62") (name "unconnected-(U1-PC6{slash}SPI_MOSI-Pad30)") (class "Default")
      (node (ref "U1") (pin "30") (pinfunction "PC6/SPI_MOSI_30") (pintype "passive"))
    )
    (net (code "63") (name "unconnected-(U1-PD0{slash}TIM3_CH2[TIM1_BKIN{slash}CLK_CCO]-Pad37)") (class "Default")
      (node (ref "U1") (pin "37") (pinfunction "PD0/TIM3_CH2[TIM1_BKIN/CLK_CCO]_37") (pintype "passive"))
    )
    (net (code "64") (name "unconnected-(U1-PD2{slash}TIM3_CH1[TIM2_CH3]-Pad39)") (class "Default")
      (node (ref "U1") (pin "39") (pinfunction "PD2/TIM3_CH1[TIM2_CH3]_39") (pintype "passive"))
    )
    (net (code "65") (name "unconnected-(U1-PD3{slash}TIM2_CH2[ADC_ETR]-Pad40)") (class "Default")
      (node (ref "U1") (pin "40") (pinfunction "PD3/TIM2_CH2[ADC_ETR]_40") (pintype "passive"))
    )
    (net (code "66") (name "unconnected-(U1-PD4{slash}TIM2_CH1{slash}[BEEP]-Pad41)") (class "Default")
      (node (ref "U1") (pin "41") (pinfunction "PD4/TIM2_CH1/[BEEP]_41") (pintype "passive"))
    )
    (net (code "67") (name "unconnected-(U1-PD5{slash}UART3_TX-Pad42)") (class "Default")
      (node (ref "U1") (pin "42") (pinfunction "PD5/UART3_TX_42") (pintype "passive"))
    )
    (net (code "68") (name "unconnected-(U1-PE0{slash}CLK_CCO-Pad36)") (class "Default")
      (node (ref "U1") (pin "36") (pinfunction "PE0/CLK_CCO_36") (pintype "passive"))
    )
    (net (code "69") (name "unconnected-(U1-PE1{slash}I2C_SCL-Pad35)") (class "Default")
      (node (ref "U1") (pin "35") (pinfunction "PE1/I2C_SCL_35") (pintype "passive"))
    )
    (net (code "70") (name "unconnected-(U1-PE2{slash}I2C_SDA-Pad34)") (class "Default")
      (node (ref "U1") (pin "34") (pinfunction "PE2/I2C_SDA_34") (pintype "passive"))
    )
    (net (code "71") (name "unconnected-(U1-PE5{slash}SPI_NSS-Pad23)") (class "Default")
      (node (ref "U1") (pin "23") (pinfunction "PE5/SPI_NSS_23") (pintype "passive"))
    )
    (net (code "72") (name "unconnected-(U2-Vref-Pad5)") (class "Default")
      (node (ref "U2") (pin "5") (pinfunction "Vref_5") (pintype "passive"))
    )
    (net (code "73") (name "unconnected-(U3-10-PadEn2)") (class "Default")
      (node (ref "U3") (pin "En2") (pinfunction "10_En2") (pintype "passive"))
    )
    (net (code "74") (name "unconnected-(U3-En1-Pad7)") (class "Default")
      (node (ref "U3") (pin "7") (pinfunction "En1_7") (pintype "passive"))
    )
    (net (code "75") (name "unconnected-(U3-InB-Pad4)") (class "Default")
      (node (ref "U3") (pin "4") (pinfunction "InB_4") (pintype "passive"))
    )
    (net (code "76") (name "unconnected-(U3-OutB-Pad13)") (class "Default")
      (node (ref "U3") (pin "13") (pinfunction "OutB_13") (pintype "passive"))
    )
    (net (code "77") (name "unconnected-(U3-Pad6)") (class "Default")
      (node (ref "U3") (pin "6") (pinfunction "6_6") (pintype "passive"))
    )
    (net (code "78") (name "unconnected-(U3-Pad11)") (class "Default")
      (node (ref "U3") (pin "11") (pinfunction "11_11") (pintype "passive"))
    )
    (net (code "79") (name "unconnected-(U4-~{MR}-Pad3)") (class "Default")
      (node (ref "U4") (pin "3") (pinfunction "~{MR}_3") (pintype "input"))
    )
  )
)
